# MCU.net
KiCad netlist of a schematic drawn in Altium Designer
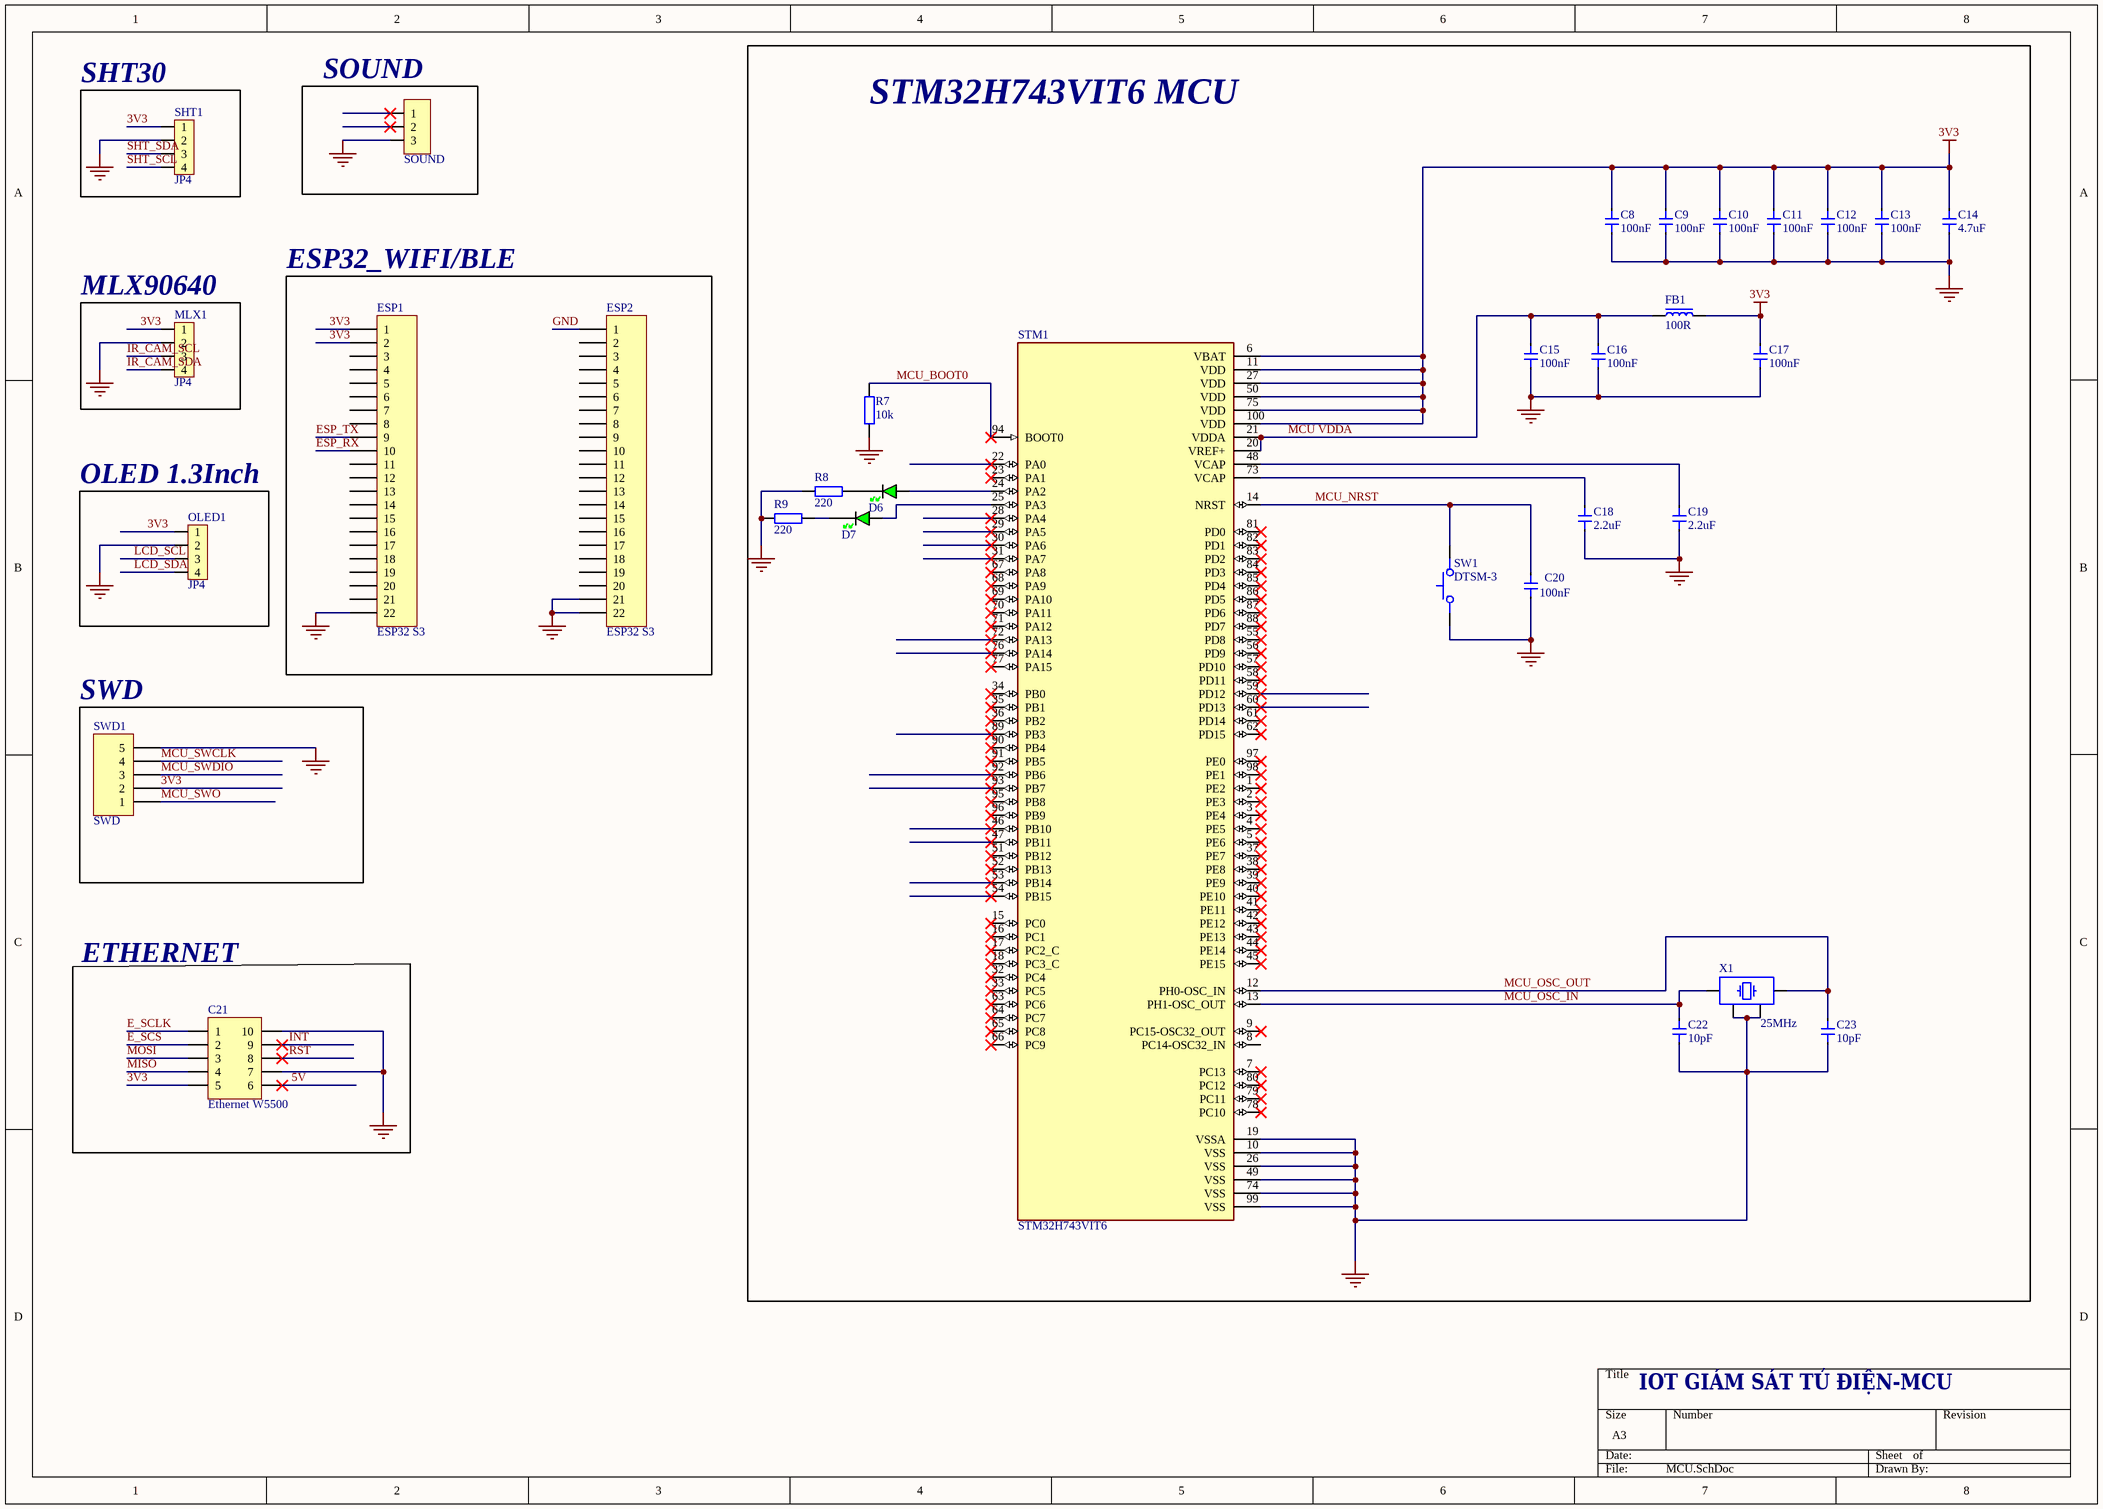
[diagram p0: MCU.SchDoc]

(export (version "E")
  (design (tool "Eeschema 10.0.6"))
  (components
    (comp (ref "C8")
      (value "100nF")
      (footprint "Cap 0805")
      (description "Capacitor SMD 0805")
      (libsource (lib "Altium_Lib_by_KhueNguyenCreator") (part "Cap 0805"))
    )
    (comp (ref "C9")
      (value "100nF")
      (footprint "Cap 0805")
      (description "Capacitor SMD 0805")
      (libsource (lib "Altium_Lib_by_KhueNguyenCreator") (part "Cap 0805"))
    )
    (comp (ref "C10")
      (value "100nF")
      (footprint "Cap 0805")
      (description "Capacitor SMD 0805")
      (libsource (lib "Altium_Lib_by_KhueNguyenCreator") (part "Cap 0805"))
    )
    (comp (ref "C11")
      (value "100nF")
      (footprint "Cap 0805")
      (description "Capacitor SMD 0805")
      (libsource (lib "Altium_Lib_by_KhueNguyenCreator") (part "Cap 0805"))
    )
    (comp (ref "C12")
      (value "100nF")
      (footprint "Cap 0805")
      (description "Capacitor SMD 0805")
      (libsource (lib "Altium_Lib_by_KhueNguyenCreator") (part "Cap 0805"))
    )
    (comp (ref "C13")
      (value "100nF")
      (footprint "Cap 0805")
      (description "Capacitor SMD 0805")
      (libsource (lib "Altium_Lib_by_KhueNguyenCreator") (part "Cap 0805"))
    )
    (comp (ref "C14")
      (value "4.7uF")
      (footprint "Cap 0805")
      (description "Capacitor SMD 0805")
      (libsource (lib "Altium_Lib_by_KhueNguyenCreator") (part "Cap 0805"))
    )
    (comp (ref "C15")
      (value "100nF")
      (footprint "Cap 0805")
      (description "Capacitor SMD 0805")
      (libsource (lib "Altium_Lib_by_KhueNguyenCreator") (part "Cap 0805"))
    )
    (comp (ref "C16")
      (value "100nF")
      (footprint "Cap 0805")
      (description "Capacitor SMD 0805")
      (libsource (lib "Altium_Lib_by_KhueNguyenCreator") (part "Cap 0805"))
    )
    (comp (ref "C17")
      (value "100nF")
      (footprint "Cap 0805")
      (description "Capacitor SMD 0805")
      (libsource (lib "Altium_Lib_by_KhueNguyenCreator") (part "Cap 0805"))
    )
    (comp (ref "C18")
      (value "2.2uF")
      (footprint "Cap 0805")
      (description "Capacitor SMD 0805")
      (libsource (lib "Altium_Lib_by_KhueNguyenCreator") (part "Cap 0805"))
    )
    (comp (ref "C19")
      (value "2.2uF")
      (footprint "Cap 0805")
      (description "Capacitor SMD 0805")
      (libsource (lib "Altium_Lib_by_KhueNguyenCreator") (part "Cap 0805"))
    )
    (comp (ref "C20")
      (value "100nF")
      (footprint "Cap 0805")
      (description "Capacitor SMD 0805")
      (libsource (lib "Altium_Lib_by_KhueNguyenCreator") (part "Cap 0805"))
    )
    (comp (ref "C21")
      (value "Ethernet W5500")
      (footprint "JP5-D2T")
      (description "WR-PHD 2.54 mm Dual Socket Header")
      (fields
        (field (name "MANUFACTURER") "Würth Elektronik eiSos GmbH")
        (field (name "PARTNO") "61301021821")
        (field (name "CREATED BY") "Karrer Zheng")
      )
      (libsource (lib "My-Library") (part "JP5x2"))
    )
    (comp (ref "C22")
      (value "10pF")
      (footprint "Cap 0805")
      (description "Capacitor SMD 0805")
      (libsource (lib "Altium_Lib_by_KhueNguyenCreator") (part "Cap 0805"))
    )
    (comp (ref "C23")
      (value "10pF")
      (footprint "Cap 0805")
      (description "Capacitor SMD 0805")
      (libsource (lib "Altium_Lib_by_KhueNguyenCreator") (part "Cap 0805"))
    )
    (comp (ref "D6")
      (value "GREEN")
      (footprint "LED_0805_GREEN")
      (description "LED 0805 GREEN SMD")
      (libsource (lib "Schematic-Lib-PhilsLab") (part "LED_0805_GREEN"))
    )
    (comp (ref "D7")
      (value "GREEN")
      (footprint "LED_0805_GREEN")
      (description "LED 0805 GREEN SMD")
      (libsource (lib "Schematic-Lib-PhilsLab") (part "LED_0805_GREEN"))
    )
    (comp (ref "ESP1")
      (value "ESP32 S3")
      (footprint "HDR1X22")
      (description "Header, 22-Pin")
      (fields (field (name "PUBLISHER") "Altium Limited"))
      (libsource (lib "My-Library") (part "Header 22"))
    )
    (comp (ref "ESP2")
      (value "ESP32 S3")
      (footprint "HDR1X22")
      (description "Header, 22-Pin")
      (fields (field (name "PUBLISHER") "Altium Limited"))
      (libsource (lib "My-Library") (part "Header 22"))
    )
    (comp (ref "FB1")
      (value "100R")
      (footprint "FB_0805")
      (description "Ferrite Bead SMD 0805")
      (libsource (lib "Schematic-Lib-PhilsLab") (part "FB_0805"))
    )
    (comp (ref "JP1")
      (value "SOUND")
      (footprint "JP 1x3 CT")
      (description "Cắm")
      (libsource (lib "Altium_Lib_by_KhueNguyenCreator") (part "JP 1x3 2.54 Cai Thang"))
    )
    (comp (ref "MLX1")
      (value "JP4")
      (footprint "JP4-C1T")
      (description "WR-PHD 2.54 mm Angled Socket Header")
      (fields
        (field (name "MANUFACTURER") "Würth Elektronik eiSos GmbH")
        (field (name "PARTNO") "613004143121")
        (field (name "CREATED BY") "Karrer Zheng")
      )
      (libsource (lib "My-Library") (part "JP4"))
    )
    (comp (ref "OLED1")
      (value "JP4")
      (footprint "JP4-C1T")
      (description "WR-PHD 2.54 mm Angled Socket Header")
      (fields
        (field (name "MANUFACTURER") "Würth Elektronik eiSos GmbH")
        (field (name "PARTNO") "613004143121")
        (field (name "CREATED BY") "Karrer Zheng")
      )
      (libsource (lib "My-Library") (part "JP4"))
    )
    (comp (ref "R7")
      (value "10k")
      (footprint "RES_0805")
      (description "Resistor SMD 0805")
      (libsource (lib "Schematic-Lib-PhilsLab") (part "RES_0805"))
    )
    (comp (ref "R8")
      (value "220")
      (footprint "RES_0805")
      (description "Resistor SMD 0805")
      (libsource (lib "Schematic-Lib-PhilsLab") (part "RES_0805"))
    )
    (comp (ref "R9")
      (value "220")
      (footprint "RES_0805")
      (description "Resistor SMD 0805")
      (libsource (lib "Schematic-Lib-PhilsLab") (part "RES_0805"))
    )
    (comp (ref "SHT1")
      (value "JP4")
      (footprint "JP4-C1T")
      (description "WR-PHD 2.54 mm Angled Socket Header")
      (fields
        (field (name "MANUFACTURER") "Würth Elektronik eiSos GmbH")
        (field (name "PARTNO") "613004143121")
        (field (name "CREATED BY") "Karrer Zheng")
      )
      (libsource (lib "My-Library") (part "JP4"))
    )
    (comp (ref "STM1")
      (value "STM32H743VIT6")
      (footprint "QFP50P1600X1600X160-100N")
      (fields (field (name "MF") "STMicroelectronics"))
      (libsource (lib "STM32H743VIT6") (part "STM32H743VIT6"))
    )
    (comp (ref "SW1")
      (value "DTSM-3")
      (footprint "DTSM-3")
      (description "Tactile Switch SMD SPST")
      (fields (field (name "MANUFACTURER") "Diptronics"))
      (libsource (lib "Schematic-Lib-PhilsLab") (part "DTSM-3"))
    )
    (comp (ref "SWD1")
      (value "SWD")
      (footprint "HDR1X5")
      (description "Header, 5-Pin")
      (fields (field (name "PUBLISHER") "Altium Limited"))
      (libsource (lib "My-Library") (part "Header 5"))
    )
    (comp (ref "X1")
      (value "25MHz")
      (footprint "XTAL_3225")
      (description "Crystal SMD 24MHz 10PPM 7pF 3225")
      (fields
        (field (name "MANUFACTURER") "Epson")
        (field (name "MANUFACTURER PART NUMBER") "TSX-3225 24.0000MF15X-AC")
      )
      (libsource (lib "Schematic-Lib-PhilsLab") (part "TSX-3225_24.0000MF15X-AC"))
    )
  )
  (nets
    (net (code "1") (name "/5V") (class "Default")
      (node (ref "C21") (pin "6") (pinfunction "6_6") (pintype "passive+no_connect"))
    )
    (net (code "2") (name "/ESP_RX") (class "Default")
      (node (ref "ESP1") (pin "10") (pinfunction "10_10") (pintype "passive"))
    )
    (net (code "3") (name "/ESP_TX") (class "Default")
      (node (ref "ESP1") (pin "9") (pinfunction "9_9") (pintype "passive"))
    )
    (net (code "4") (name "/E_SCLK") (class "Default")
      (node (ref "C21") (pin "1") (pinfunction "1_1") (pintype "passive"))
    )
    (net (code "5") (name "/E_SCS") (class "Default")
      (node (ref "C21") (pin "2") (pinfunction "2_2") (pintype "passive"))
    )
    (net (code "6") (name "/INT") (class "Default")
      (node (ref "C21") (pin "9") (pinfunction "9_9") (pintype "passive+no_connect"))
    )
    (net (code "7") (name "/IR_CAM_SCL") (class "Default")
      (node (ref "MLX1") (pin "3") (pinfunction "3_3") (pintype "passive"))
    )
    (net (code "8") (name "/IR_CAM_SDA") (class "Default")
      (node (ref "MLX1") (pin "4") (pinfunction "4_4") (pintype "passive"))
    )
    (net (code "9") (name "/LCD_SCL") (class "Default")
      (node (ref "OLED1") (pin "3") (pinfunction "3_3") (pintype "passive"))
    )
    (net (code "10") (name "/LCD_SDA") (class "Default")
      (node (ref "OLED1") (pin "4") (pinfunction "4_4") (pintype "passive"))
    )
    (net (code "11") (name "/MCU VDDA") (class "Default")
      (node (ref "C15") (pin "1") (pinfunction "1_1") (pintype "passive"))
      (node (ref "C16") (pin "1") (pinfunction "1_1") (pintype "passive"))
      (node (ref "FB1") (pin "1") (pinfunction "1_1") (pintype "passive"))
      (node (ref "STM1") (pin "20") (pinfunction "VREF+_20") (pintype "power_in"))
      (node (ref "STM1") (pin "21") (pinfunction "VDDA_21") (pintype "power_in"))
    )
    (net (code "12") (name "/MCU_BOOT0") (class "Default")
      (node (ref "R7") (pin "2") (pinfunction "2_2") (pintype "passive"))
      (node (ref "STM1") (pin "94") (pinfunction "BOOT0_94") (pintype "input"))
    )
    (net (code "13") (name "/MCU_NRST") (class "Default")
      (node (ref "C20") (pin "1") (pinfunction "1_1") (pintype "passive"))
      (node (ref "STM1") (pin "14") (pinfunction "NRST_14") (pintype "bidirectional"))
      (node (ref "SW1") (pin "2") (pintype "passive"))
    )
    (net (code "14") (name "/MCU_OSC_IN") (class "Default")
      (node (ref "C22") (pin "1") (pinfunction "1_1") (pintype "passive"))
      (node (ref "STM1") (pin "13") (pinfunction "PH1-OSC_OUT_13") (pintype "bidirectional"))
      (node (ref "X1") (pin "1") (pinfunction "1_1") (pintype "passive"))
    )
    (net (code "15") (name "/MCU_OSC_OUT") (class "Default")
      (node (ref "C23") (pin "1") (pinfunction "1_1") (pintype "passive"))
      (node (ref "STM1") (pin "12") (pinfunction "PH0-OSC_IN_12") (pintype "bidirectional"))
      (node (ref "X1") (pin "3") (pinfunction "3_3") (pintype "passive"))
    )
    (net (code "16") (name "/MCU_SWCLK") (class "Default")
      (node (ref "SWD1") (pin "4") (pinfunction "4_4") (pintype "passive"))
    )
    (net (code "17") (name "/MCU_SWDIO") (class "Default")
      (node (ref "SWD1") (pin "3") (pinfunction "3_3") (pintype "passive"))
    )
    (net (code "18") (name "/MCU_SWO") (class "Default")
      (node (ref "SWD1") (pin "1") (pinfunction "1_1") (pintype "passive"))
    )
    (net (code "19") (name "/MISO") (class "Default")
      (node (ref "C21") (pin "4") (pinfunction "4_4") (pintype "passive"))
    )
    (net (code "20") (name "/MOSI") (class "Default")
      (node (ref "C21") (pin "3") (pinfunction "3_3") (pintype "passive"))
    )
    (net (code "21") (name "/RST") (class "Default")
      (node (ref "C21") (pin "8") (pinfunction "8_8") (pintype "passive+no_connect"))
    )
    (net (code "22") (name "/SHT_SCL") (class "Default")
      (node (ref "SHT1") (pin "4") (pinfunction "4_4") (pintype "passive"))
    )
    (net (code "23") (name "/SHT_SDA") (class "Default")
      (node (ref "SHT1") (pin "3") (pinfunction "3_3") (pintype "passive"))
    )
    (net (code "24") (name "3V3") (class "Default")
      (node (ref "C10") (pin "1") (pinfunction "1_1") (pintype "passive"))
      (node (ref "C11") (pin "1") (pinfunction "1_1") (pintype "passive"))
      (node (ref "C12") (pin "1") (pinfunction "1_1") (pintype "passive"))
      (node (ref "C13") (pin "1") (pinfunction "1_1") (pintype "passive"))
      (node (ref "C14") (pin "1") (pinfunction "1_1") (pintype "passive"))
      (node (ref "C17") (pin "1") (pinfunction "1_1") (pintype "passive"))
      (node (ref "C21") (pin "5") (pinfunction "5_5") (pintype "passive"))
      (node (ref "C8") (pin "1") (pinfunction "1_1") (pintype "passive"))
      (node (ref "C9") (pin "1") (pinfunction "1_1") (pintype "passive"))
      (node (ref "ESP1") (pin "1") (pinfunction "1_1") (pintype "passive"))
      (node (ref "ESP1") (pin "2") (pinfunction "2_2") (pintype "passive"))
      (node (ref "FB1") (pin "2") (pinfunction "2_2") (pintype "passive"))
      (node (ref "MLX1") (pin "1") (pinfunction "1_1") (pintype "passive"))
      (node (ref "OLED1") (pin "1") (pinfunction "1_1") (pintype "passive"))
      (node (ref "SHT1") (pin "1") (pinfunction "1_1") (pintype "passive"))
      (node (ref "STM1") (pin "100") (pinfunction "VDD_100") (pintype "power_in"))
      (node (ref "STM1") (pin "11") (pinfunction "VDD_11") (pintype "power_in"))
      (node (ref "STM1") (pin "27") (pinfunction "VDD_27") (pintype "power_in"))
      (node (ref "STM1") (pin "50") (pinfunction "VDD_50") (pintype "power_in"))
      (node (ref "STM1") (pin "6") (pinfunction "VBAT_6") (pintype "power_in"))
      (node (ref "STM1") (pin "75") (pinfunction "VDD_75") (pintype "power_in"))
      (node (ref "SWD1") (pin "2") (pinfunction "2_2") (pintype "passive"))
    )
    (net (code "25") (name "GND") (class "Default")
      (node (ref "C10") (pin "2") (pinfunction "2_2") (pintype "passive"))
      (node (ref "C11") (pin "2") (pinfunction "2_2") (pintype "passive"))
      (node (ref "C12") (pin "2") (pinfunction "2_2") (pintype "passive"))
      (node (ref "C13") (pin "2") (pinfunction "2_2") (pintype "passive"))
      (node (ref "C14") (pin "2") (pinfunction "2_2") (pintype "passive"))
      (node (ref "C15") (pin "2") (pinfunction "2_2") (pintype "passive"))
      (node (ref "C16") (pin "2") (pinfunction "2_2") (pintype "passive"))
      (node (ref "C17") (pin "2") (pinfunction "2_2") (pintype "passive"))
      (node (ref "C18") (pin "1") (pinfunction "1_1") (pintype "passive"))
      (node (ref "C19") (pin "2") (pinfunction "2_2") (pintype "passive"))
      (node (ref "C20") (pin "2") (pinfunction "2_2") (pintype "passive"))
      (node (ref "C21") (pin "10") (pinfunction "10_10") (pintype "passive"))
      (node (ref "C21") (pin "7") (pinfunction "7_7") (pintype "passive"))
      (node (ref "C22") (pin "2") (pinfunction "2_2") (pintype "passive"))
      (node (ref "C23") (pin "2") (pinfunction "2_2") (pintype "passive"))
      (node (ref "C8") (pin "2") (pinfunction "2_2") (pintype "passive"))
      (node (ref "C9") (pin "2") (pinfunction "2_2") (pintype "passive"))
      (node (ref "ESP1") (pin "22") (pinfunction "22_22") (pintype "passive"))
      (node (ref "ESP2") (pin "1") (pinfunction "1_1") (pintype "passive"))
      (node (ref "ESP2") (pin "21") (pinfunction "21_21") (pintype "passive"))
      (node (ref "ESP2") (pin "22") (pinfunction "22_22") (pintype "passive"))
      (node (ref "JP1") (pin "3") (pinfunction "3_3") (pintype "passive"))
      (node (ref "MLX1") (pin "2") (pinfunction "2_2") (pintype "passive"))
      (node (ref "OLED1") (pin "2") (pinfunction "2_2") (pintype "passive"))
      (node (ref "R7") (pin "1") (pinfunction "1_1") (pintype "passive"))
      (node (ref "R8") (pin "1") (pinfunction "1_1") (pintype "passive"))
      (node (ref "R9") (pin "1") (pinfunction "1_1") (pintype "passive"))
      (node (ref "SHT1") (pin "2") (pinfunction "2_2") (pintype "passive"))
      (node (ref "STM1") (pin "10") (pinfunction "VSS_10") (pintype "power_in"))
      (node (ref "STM1") (pin "19") (pinfunction "VSSA_19") (pintype "power_in"))
      (node (ref "STM1") (pin "26") (pinfunction "VSS_26") (pintype "power_in"))
      (node (ref "STM1") (pin "49") (pinfunction "VSS_49") (pintype "power_in"))
      (node (ref "STM1") (pin "74") (pinfunction "VSS_74") (pintype "power_in"))
      (node (ref "STM1") (pin "99") (pinfunction "VSS_99") (pintype "power_in"))
      (node (ref "SW1") (pin "1") (pintype "passive"))
      (node (ref "SWD1") (pin "5") (pinfunction "5_5") (pintype "passive"))
      (node (ref "X1") (pin "2") (pinfunction "2_2") (pintype "passive"))
      (node (ref "X1") (pin "4") (pinfunction "4_4") (pintype "passive"))
    )
    (net (code "26") (name "Net-(C18-Pad2)") (class "Default")
      (node (ref "C18") (pin "2") (pinfunction "2_2") (pintype "passive"))
      (node (ref "STM1") (pin "73") (pinfunction "VCAP_73") (pintype "power_in"))
    )
    (net (code "27") (name "Net-(C19-Pad1)") (class "Default")
      (node (ref "C19") (pin "1") (pinfunction "1_1") (pintype "passive"))
      (node (ref "STM1") (pin "48") (pinfunction "VCAP_48") (pintype "power_in"))
    )
    (net (code "28") (name "Net-(D6-PadK)") (class "Default")
      (node (ref "D6") (pin "K") (pinfunction "K_K") (pintype "passive"))
      (node (ref "R8") (pin "2") (pinfunction "2_2") (pintype "passive"))
    )
    (net (code "29") (name "Net-(D7-PadK)") (class "Default")
      (node (ref "D7") (pin "K") (pinfunction "K_K") (pintype "passive"))
      (node (ref "R9") (pin "2") (pinfunction "2_2") (pintype "passive"))
    )
    (net (code "30") (name "Net-(STM1-PA2)") (class "Default")
      (node (ref "D6") (pin "A") (pinfunction "A_A") (pintype "passive"))
      (node (ref "STM1") (pin "24") (pinfunction "PA2_24") (pintype "bidirectional"))
    )
    (net (code "31") (name "Net-(STM1-PA3)") (class "Default")
      (node (ref "D7") (pin "A") (pinfunction "A_A") (pintype "passive"))
      (node (ref "STM1") (pin "25") (pinfunction "PA3_25") (pintype "bidirectional"))
    )
    (net (code "32") (name "unconnected-(ESP1-Pad3)") (class "Default")
      (node (ref "ESP1") (pin "3") (pinfunction "3_3") (pintype "passive"))
    )
    (net (code "33") (name "unconnected-(ESP1-Pad4)") (class "Default")
      (node (ref "ESP1") (pin "4") (pinfunction "4_4") (pintype "passive"))
    )
    (net (code "34") (name "unconnected-(ESP1-Pad5)") (class "Default")
      (node (ref "ESP1") (pin "5") (pinfunction "5_5") (pintype "passive"))
    )
    (net (code "35") (name "unconnected-(ESP1-Pad6)") (class "Default")
      (node (ref "ESP1") (pin "6") (pinfunction "6_6") (pintype "passive"))
    )
    (net (code "36") (name "unconnected-(ESP1-Pad7)") (class "Default")
      (node (ref "ESP1") (pin "7") (pinfunction "7_7") (pintype "passive"))
    )
    (net (code "37") (name "unconnected-(ESP1-Pad8)") (class "Default")
      (node (ref "ESP1") (pin "8") (pinfunction "8_8") (pintype "passive"))
    )
    (net (code "38") (name "unconnected-(ESP1-Pad11)") (class "Default")
      (node (ref "ESP1") (pin "11") (pinfunction "11_11") (pintype "passive"))
    )
    (net (code "39") (name "unconnected-(ESP1-Pad12)") (class "Default")
      (node (ref "ESP1") (pin "12") (pinfunction "12_12") (pintype "passive"))
    )
    (net (code "40") (name "unconnected-(ESP1-Pad13)") (class "Default")
      (node (ref "ESP1") (pin "13") (pinfunction "13_13") (pintype "passive"))
    )
    (net (code "41") (name "unconnected-(ESP1-Pad14)") (class "Default")
      (node (ref "ESP1") (pin "14") (pinfunction "14_14") (pintype "passive"))
    )
    (net (code "42") (name "unconnected-(ESP1-Pad15)") (class "Default")
      (node (ref "ESP1") (pin "15") (pinfunction "15_15") (pintype "passive"))
    )
    (net (code "43") (name "unconnected-(ESP1-Pad16)") (class "Default")
      (node (ref "ESP1") (pin "16") (pinfunction "16_16") (pintype "passive"))
    )
    (net (code "44") (name "unconnected-(ESP1-Pad17)") (class "Default")
      (node (ref "ESP1") (pin "17") (pinfunction "17_17") (pintype "passive"))
    )
    (net (code "45") (name "unconnected-(ESP1-Pad18)") (class "Default")
      (node (ref "ESP1") (pin "18") (pinfunction "18_18") (pintype "passive"))
    )
    (net (code "46") (name "unconnected-(ESP1-Pad19)") (class "Default")
      (node (ref "ESP1") (pin "19") (pinfunction "19_19") (pintype "passive"))
    )
    (net (code "47") (name "unconnected-(ESP1-Pad20)") (class "Default")
      (node (ref "ESP1") (pin "20") (pinfunction "20_20") (pintype "passive"))
    )
    (net (code "48") (name "unconnected-(ESP1-Pad21)") (class "Default")
      (node (ref "ESP1") (pin "21") (pinfunction "21_21") (pintype "passive"))
    )
    (net (code "49") (name "unconnected-(ESP2-Pad2)") (class "Default")
      (node (ref "ESP2") (pin "2") (pinfunction "2_2") (pintype "passive"))
    )
    (net (code "50") (name "unconnected-(ESP2-Pad3)") (class "Default")
      (node (ref "ESP2") (pin "3") (pinfunction "3_3") (pintype "passive"))
    )
    (net (code "51") (name "unconnected-(ESP2-Pad4)") (class "Default")
      (node (ref "ESP2") (pin "4") (pinfunction "4_4") (pintype "passive"))
    )
    (net (code "52") (name "unconnected-(ESP2-Pad5)") (class "Default")
      (node (ref "ESP2") (pin "5") (pinfunction "5_5") (pintype "passive"))
    )
    (net (code "53") (name "unconnected-(ESP2-Pad6)") (class "Default")
      (node (ref "ESP2") (pin "6") (pinfunction "6_6") (pintype "passive"))
    )
    (net (code "54") (name "unconnected-(ESP2-Pad7)") (class "Default")
      (node (ref "ESP2") (pin "7") (pinfunction "7_7") (pintype "passive"))
    )
    (net (code "55") (name "unconnected-(ESP2-Pad8)") (class "Default")
      (node (ref "ESP2") (pin "8") (pinfunction "8_8") (pintype "passive"))
    )
    (net (code "56") (name "unconnected-(ESP2-Pad9)") (class "Default")
      (node (ref "ESP2") (pin "9") (pinfunction "9_9") (pintype "passive"))
    )
    (net (code "57") (name "unconnected-(ESP2-Pad10)") (class "Default")
      (node (ref "ESP2") (pin "10") (pinfunction "10_10") (pintype "passive"))
    )
    (net (code "58") (name "unconnected-(ESP2-Pad11)") (class "Default")
      (node (ref "ESP2") (pin "11") (pinfunction "11_11") (pintype "passive"))
    )
    (net (code "59") (name "unconnected-(ESP2-Pad12)") (class "Default")
      (node (ref "ESP2") (pin "12") (pinfunction "12_12") (pintype "passive"))
    )
    (net (code "60") (name "unconnected-(ESP2-Pad13)") (class "Default")
      (node (ref "ESP2") (pin "13") (pinfunction "13_13") (pintype "passive"))
    )
    (net (code "61") (name "unconnected-(ESP2-Pad14)") (class "Default")
      (node (ref "ESP2") (pin "14") (pinfunction "14_14") (pintype "passive"))
    )
    (net (code "62") (name "unconnected-(ESP2-Pad15)") (class "Default")
      (node (ref "ESP2") (pin "15") (pinfunction "15_15") (pintype "passive"))
    )
    (net (code "63") (name "unconnected-(ESP2-Pad16)") (class "Default")
      (node (ref "ESP2") (pin "16") (pinfunction "16_16") (pintype "passive"))
    )
    (net (code "64") (name "unconnected-(ESP2-Pad17)") (class "Default")
      (node (ref "ESP2") (pin "17") (pinfunction "17_17") (pintype "passive"))
    )
    (net (code "65") (name "unconnected-(ESP2-Pad18)") (class "Default")
      (node (ref "ESP2") (pin "18") (pinfunction "18_18") (pintype "passive"))
    )
    (net (code "66") (name "unconnected-(ESP2-Pad19)") (class "Default")
      (node (ref "ESP2") (pin "19") (pinfunction "19_19") (pintype "passive"))
    )
    (net (code "67") (name "unconnected-(ESP2-Pad20)") (class "Default")
      (node (ref "ESP2") (pin "20") (pinfunction "20_20") (pintype "passive"))
    )
    (net (code "68") (name "unconnected-(JP1-Pad1)") (class "Default")
      (node (ref "JP1") (pin "1") (pinfunction "1_1") (pintype "passive+no_connect"))
    )
    (net (code "69") (name "unconnected-(JP1-Pad2)") (class "Default")
      (node (ref "JP1") (pin "2") (pinfunction "2_2") (pintype "passive+no_connect"))
    )
    (net (code "70") (name "unconnected-(STM1-PA0-Pad22)") (class "Default")
      (node (ref "STM1") (pin "22") (pinfunction "PA0_22") (pintype "bidirectional+no_connect"))
    )
    (net (code "71") (name "unconnected-(STM1-PA1-Pad23)") (class "Default")
      (node (ref "STM1") (pin "23") (pinfunction "PA1_23") (pintype "bidirectional+no_connect"))
    )
    (net (code "72") (name "unconnected-(STM1-PA4-Pad28)") (class "Default")
      (node (ref "STM1") (pin "28") (pinfunction "PA4_28") (pintype "bidirectional+no_connect"))
    )
    (net (code "73") (name "unconnected-(STM1-PA5-Pad29)") (class "Default")
      (node (ref "STM1") (pin "29") (pinfunction "PA5_29") (pintype "bidirectional+no_connect"))
    )
    (net (code "74") (name "unconnected-(STM1-PA6-Pad30)") (class "Default")
      (node (ref "STM1") (pin "30") (pinfunction "PA6_30") (pintype "bidirectional+no_connect"))
    )
    (net (code "75") (name "unconnected-(STM1-PA7-Pad31)") (class "Default")
      (node (ref "STM1") (pin "31") (pinfunction "PA7_31") (pintype "bidirectional+no_connect"))
    )
    (net (code "76") (name "unconnected-(STM1-PA8-Pad67)") (class "Default")
      (node (ref "STM1") (pin "67") (pinfunction "PA8_67") (pintype "bidirectional+no_connect"))
    )
    (net (code "77") (name "unconnected-(STM1-PA9-Pad68)") (class "Default")
      (node (ref "STM1") (pin "68") (pinfunction "PA9_68") (pintype "bidirectional+no_connect"))
    )
    (net (code "78") (name "unconnected-(STM1-PA10-Pad69)") (class "Default")
      (node (ref "STM1") (pin "69") (pinfunction "PA10_69") (pintype "bidirectional+no_connect"))
    )
    (net (code "79") (name "unconnected-(STM1-PA11-Pad70)") (class "Default")
      (node (ref "STM1") (pin "70") (pinfunction "PA11_70") (pintype "bidirectional+no_connect"))
    )
    (net (code "80") (name "unconnected-(STM1-PA12-Pad71)") (class "Default")
      (node (ref "STM1") (pin "71") (pinfunction "PA12_71") (pintype "bidirectional+no_connect"))
    )
    (net (code "81") (name "unconnected-(STM1-PA13-Pad72)") (class "Default")
      (node (ref "STM1") (pin "72") (pinfunction "PA13_72") (pintype "bidirectional+no_connect"))
    )
    (net (code "82") (name "unconnected-(STM1-PA14-Pad76)") (class "Default")
      (node (ref "STM1") (pin "76") (pinfunction "PA14_76") (pintype "bidirectional+no_connect"))
    )
    (net (code "83") (name "unconnected-(STM1-PA15-Pad77)") (class "Default")
      (node (ref "STM1") (pin "77") (pinfunction "PA15_77") (pintype "bidirectional+no_connect"))
    )
    (net (code "84") (name "unconnected-(STM1-PB0-Pad34)") (class "Default")
      (node (ref "STM1") (pin "34") (pinfunction "PB0_34") (pintype "bidirectional+no_connect"))
    )
    (net (code "85") (name "unconnected-(STM1-PB1-Pad35)") (class "Default")
      (node (ref "STM1") (pin "35") (pinfunction "PB1_35") (pintype "bidirectional+no_connect"))
    )
    (net (code "86") (name "unconnected-(STM1-PB2-Pad36)") (class "Default")
      (node (ref "STM1") (pin "36") (pinfunction "PB2_36") (pintype "bidirectional+no_connect"))
    )
    (net (code "87") (name "unconnected-(STM1-PB3-Pad89)") (class "Default")
      (node (ref "STM1") (pin "89") (pinfunction "PB3_89") (pintype "bidirectional+no_connect"))
    )
    (net (code "88") (name "unconnected-(STM1-PB4-Pad90)") (class "Default")
      (node (ref "STM1") (pin "90") (pinfunction "PB4_90") (pintype "bidirectional+no_connect"))
    )
    (net (code "89") (name "unconnected-(STM1-PB5-Pad91)") (class "Default")
      (node (ref "STM1") (pin "91") (pinfunction "PB5_91") (pintype "bidirectional+no_connect"))
    )
    (net (code "90") (name "unconnected-(STM1-PB6-Pad92)") (class "Default")
      (node (ref "STM1") (pin "92") (pinfunction "PB6_92") (pintype "bidirectional+no_connect"))
    )
    (net (code "91") (name "unconnected-(STM1-PB7-Pad93)") (class "Default")
      (node (ref "STM1") (pin "93") (pinfunction "PB7_93") (pintype "bidirectional+no_connect"))
    )
    (net (code "92") (name "unconnected-(STM1-PB8-Pad95)") (class "Default")
      (node (ref "STM1") (pin "95") (pinfunction "PB8_95") (pintype "bidirectional+no_connect"))
    )
    (net (code "93") (name "unconnected-(STM1-PB9-Pad96)") (class "Default")
      (node (ref "STM1") (pin "96") (pinfunction "PB9_96") (pintype "bidirectional+no_connect"))
    )
    (net (code "94") (name "unconnected-(STM1-PB10-Pad46)") (class "Default")
      (node (ref "STM1") (pin "46") (pinfunction "PB10_46") (pintype "bidirectional+no_connect"))
    )
    (net (code "95") (name "unconnected-(STM1-PB11-Pad47)") (class "Default")
      (node (ref "STM1") (pin "47") (pinfunction "PB11_47") (pintype "bidirectional+no_connect"))
    )
    (net (code "96") (name "unconnected-(STM1-PB12-Pad51)") (class "Default")
      (node (ref "STM1") (pin "51") (pinfunction "PB12_51") (pintype "bidirectional+no_connect"))
    )
    (net (code "97") (name "unconnected-(STM1-PB13-Pad52)") (class "Default")
      (node (ref "STM1") (pin "52") (pinfunction "PB13_52") (pintype "bidirectional+no_connect"))
    )
    (net (code "98") (name "unconnected-(STM1-PB14-Pad53)") (class "Default")
      (node (ref "STM1") (pin "53") (pinfunction "PB14_53") (pintype "bidirectional+no_connect"))
    )
    (net (code "99") (name "unconnected-(STM1-PB15-Pad54)") (class "Default")
      (node (ref "STM1") (pin "54") (pinfunction "PB15_54") (pintype "bidirectional+no_connect"))
    )
    (net (code "100") (name "unconnected-(STM1-PC0-Pad15)") (class "Default")
      (node (ref "STM1") (pin "15") (pinfunction "PC0_15") (pintype "bidirectional+no_connect"))
    )
    (net (code "101") (name "unconnected-(STM1-PC1-Pad16)") (class "Default")
      (node (ref "STM1") (pin "16") (pinfunction "PC1_16") (pintype "bidirectional+no_connect"))
    )
    (net (code "102") (name "unconnected-(STM1-PC2_C-Pad17)") (class "Default")
      (node (ref "STM1") (pin "17") (pinfunction "PC2_C_17") (pintype "bidirectional+no_connect"))
    )
    (net (code "103") (name "unconnected-(STM1-PC3_C-Pad18)") (class "Default")
      (node (ref "STM1") (pin "18") (pinfunction "PC3_C_18") (pintype "bidirectional+no_connect"))
    )
    (net (code "104") (name "unconnected-(STM1-PC4-Pad32)") (class "Default")
      (node (ref "STM1") (pin "32") (pinfunction "PC4_32") (pintype "bidirectional+no_connect"))
    )
    (net (code "105") (name "unconnected-(STM1-PC5-Pad33)") (class "Default")
      (node (ref "STM1") (pin "33") (pinfunction "PC5_33") (pintype "bidirectional+no_connect"))
    )
    (net (code "106") (name "unconnected-(STM1-PC6-Pad63)") (class "Default")
      (node (ref "STM1") (pin "63") (pinfunction "PC6_63") (pintype "bidirectional+no_connect"))
    )
    (net (code "107") (name "unconnected-(STM1-PC7-Pad64)") (class "Default")
      (node (ref "STM1") (pin "64") (pinfunction "PC7_64") (pintype "bidirectional+no_connect"))
    )
    (net (code "108") (name "unconnected-(STM1-PC8-Pad65)") (class "Default")
      (node (ref "STM1") (pin "65") (pinfunction "PC8_65") (pintype "bidirectional+no_connect"))
    )
    (net (code "109") (name "unconnected-(STM1-PC9-Pad66)") (class "Default")
      (node (ref "STM1") (pin "66") (pinfunction "PC9_66") (pintype "bidirectional+no_connect"))
    )
    (net (code "110") (name "unconnected-(STM1-PC10-Pad78)") (class "Default")
      (node (ref "STM1") (pin "78") (pinfunction "PC10_78") (pintype "bidirectional+no_connect"))
    )
    (net (code "111") (name "unconnected-(STM1-PC11-Pad79)") (class "Default")
      (node (ref "STM1") (pin "79") (pinfunction "PC11_79") (pintype "bidirectional+no_connect"))
    )
    (net (code "112") (name "unconnected-(STM1-PC12-Pad80)") (class "Default")
      (node (ref "STM1") (pin "80") (pinfunction "PC12_80") (pintype "bidirectional+no_connect"))
    )
    (net (code "113") (name "unconnected-(STM1-PC13-Pad7)") (class "Default")
      (node (ref "STM1") (pin "7") (pinfunction "PC13_7") (pintype "bidirectional+no_connect"))
    )
    (net (code "114") (name "unconnected-(STM1-PC14-OSC32_IN-Pad8)") (class "Default")
      (node (ref "STM1") (pin "8") (pinfunction "PC14-OSC32_IN_8") (pintype "bidirectional"))
    )
    (net (code "115") (name "unconnected-(STM1-PC15-OSC32_OUT-Pad9)") (class "Default")
      (node (ref "STM1") (pin "9") (pinfunction "PC15-OSC32_OUT_9") (pintype "bidirectional+no_connect"))
    )
    (net (code "116") (name "unconnected-(STM1-PD0-Pad81)") (class "Default")
      (node (ref "STM1") (pin "81") (pinfunction "PD0_81") (pintype "bidirectional+no_connect"))
    )
    (net (code "117") (name "unconnected-(STM1-PD1-Pad82)") (class "Default")
      (node (ref "STM1") (pin "82") (pinfunction "PD1_82") (pintype "bidirectional+no_connect"))
    )
    (net (code "118") (name "unconnected-(STM1-PD2-Pad83)") (class "Default")
      (node (ref "STM1") (pin "83") (pinfunction "PD2_83") (pintype "bidirectional+no_connect"))
    )
    (net (code "119") (name "unconnected-(STM1-PD3-Pad84)") (class "Default")
      (node (ref "STM1") (pin "84") (pinfunction "PD3_84") (pintype "bidirectional+no_connect"))
    )
    (net (code "120") (name "unconnected-(STM1-PD4-Pad85)") (class "Default")
      (node (ref "STM1") (pin "85") (pinfunction "PD4_85") (pintype "bidirectional+no_connect"))
    )
    (net (code "121") (name "unconnected-(STM1-PD5-Pad86)") (class "Default")
      (node (ref "STM1") (pin "86") (pinfunction "PD5_86") (pintype "bidirectional+no_connect"))
    )
    (net (code "122") (name "unconnected-(STM1-PD6-Pad87)") (class "Default")
      (node (ref "STM1") (pin "87") (pinfunction "PD6_87") (pintype "bidirectional+no_connect"))
    )
    (net (code "123") (name "unconnected-(STM1-PD7-Pad88)") (class "Default")
      (node (ref "STM1") (pin "88") (pinfunction "PD7_88") (pintype "bidirectional+no_connect"))
    )
    (net (code "124") (name "unconnected-(STM1-PD8-Pad55)") (class "Default")
      (node (ref "STM1") (pin "55") (pinfunction "PD8_55") (pintype "bidirectional+no_connect"))
    )
    (net (code "125") (name "unconnected-(STM1-PD9-Pad56)") (class "Default")
      (node (ref "STM1") (pin "56") (pinfunction "PD9_56") (pintype "bidirectional+no_connect"))
    )
    (net (code "126") (name "unconnected-(STM1-PD10-Pad57)") (class "Default")
      (node (ref "STM1") (pin "57") (pinfunction "PD10_57") (pintype "bidirectional+no_connect"))
    )
    (net (code "127") (name "unconnected-(STM1-PD11-Pad58)") (class "Default")
      (node (ref "STM1") (pin "58") (pinfunction "PD11_58") (pintype "bidirectional+no_connect"))
    )
    (net (code "128") (name "unconnected-(STM1-PD12-Pad59)") (class "Default")
      (node (ref "STM1") (pin "59") (pinfunction "PD12_59") (pintype "bidirectional+no_connect"))
    )
    (net (code "129") (name "unconnected-(STM1-PD13-Pad60)") (class "Default")
      (node (ref "STM1") (pin "60") (pinfunction "PD13_60") (pintype "bidirectional+no_connect"))
    )
    (net (code "130") (name "unconnected-(STM1-PD14-Pad61)") (class "Default")
      (node (ref "STM1") (pin "61") (pinfunction "PD14_61") (pintype "bidirectional+no_connect"))
    )
    (net (code "131") (name "unconnected-(STM1-PD15-Pad62)") (class "Default")
      (node (ref "STM1") (pin "62") (pinfunction "PD15_62") (pintype "bidirectional+no_connect"))
    )
    (net (code "132") (name "unconnected-(STM1-PE0-Pad97)") (class "Default")
      (node (ref "STM1") (pin "97") (pinfunction "PE0_97") (pintype "bidirectional+no_connect"))
    )
    (net (code "133") (name "unconnected-(STM1-PE1-Pad98)") (class "Default")
      (node (ref "STM1") (pin "98") (pinfunction "PE1_98") (pintype "bidirectional+no_connect"))
    )
    (net (code "134") (name "unconnected-(STM1-PE2-Pad1)") (class "Default")
      (node (ref "STM1") (pin "1") (pinfunction "PE2_1") (pintype "bidirectional+no_connect"))
    )
    (net (code "135") (name "unconnected-(STM1-PE3-Pad2)") (class "Default")
      (node (ref "STM1") (pin "2") (pinfunction "PE3_2") (pintype "bidirectional+no_connect"))
    )
    (net (code "136") (name "unconnected-(STM1-PE4-Pad3)") (class "Default")
      (node (ref "STM1") (pin "3") (pinfunction "PE4_3") (pintype "bidirectional+no_connect"))
    )
    (net (code "137") (name "unconnected-(STM1-PE5-Pad4)") (class "Default")
      (node (ref "STM1") (pin "4") (pinfunction "PE5_4") (pintype "bidirectional+no_connect"))
    )
    (net (code "138") (name "unconnected-(STM1-PE6-Pad5)") (class "Default")
      (node (ref "STM1") (pin "5") (pinfunction "PE6_5") (pintype "bidirectional+no_connect"))
    )
    (net (code "139") (name "unconnected-(STM1-PE7-Pad37)") (class "Default")
      (node (ref "STM1") (pin "37") (pinfunction "PE7_37") (pintype "bidirectional+no_connect"))
    )
    (net (code "140") (name "unconnected-(STM1-PE8-Pad38)") (class "Default")
      (node (ref "STM1") (pin "38") (pinfunction "PE8_38") (pintype "bidirectional+no_connect"))
    )
    (net (code "141") (name "unconnected-(STM1-PE9-Pad39)") (class "Default")
      (node (ref "STM1") (pin "39") (pinfunction "PE9_39") (pintype "bidirectional+no_connect"))
    )
    (net (code "142") (name "unconnected-(STM1-PE10-Pad40)") (class "Default")
      (node (ref "STM1") (pin "40") (pinfunction "PE10_40") (pintype "bidirectional+no_connect"))
    )
    (net (code "143") (name "unconnected-(STM1-PE11-Pad41)") (class "Default")
      (node (ref "STM1") (pin "41") (pinfunction "PE11_41") (pintype "bidirectional+no_connect"))
    )
    (net (code "144") (name "unconnected-(STM1-PE12-Pad42)") (class "Default")
      (node (ref "STM1") (pin "42") (pinfunction "PE12_42") (pintype "bidirectional+no_connect"))
    )
    (net (code "145") (name "unconnected-(STM1-PE13-Pad43)") (class "Default")
      (node (ref "STM1") (pin "43") (pinfunction "PE13_43") (pintype "bidirectional+no_connect"))
    )
    (net (code "146") (name "unconnected-(STM1-PE14-Pad44)") (class "Default")
      (node (ref "STM1") (pin "44") (pinfunction "PE14_44") (pintype "bidirectional+no_connect"))
    )
    (net (code "147") (name "unconnected-(STM1-PE15-Pad45)") (class "Default")
      (node (ref "STM1") (pin "45") (pinfunction "PE15_45") (pintype "bidirectional+no_connect"))
    )
  )
)
